# adapter_board_max86916.net
KiCad netlist of a schematic drawn in EAGLE
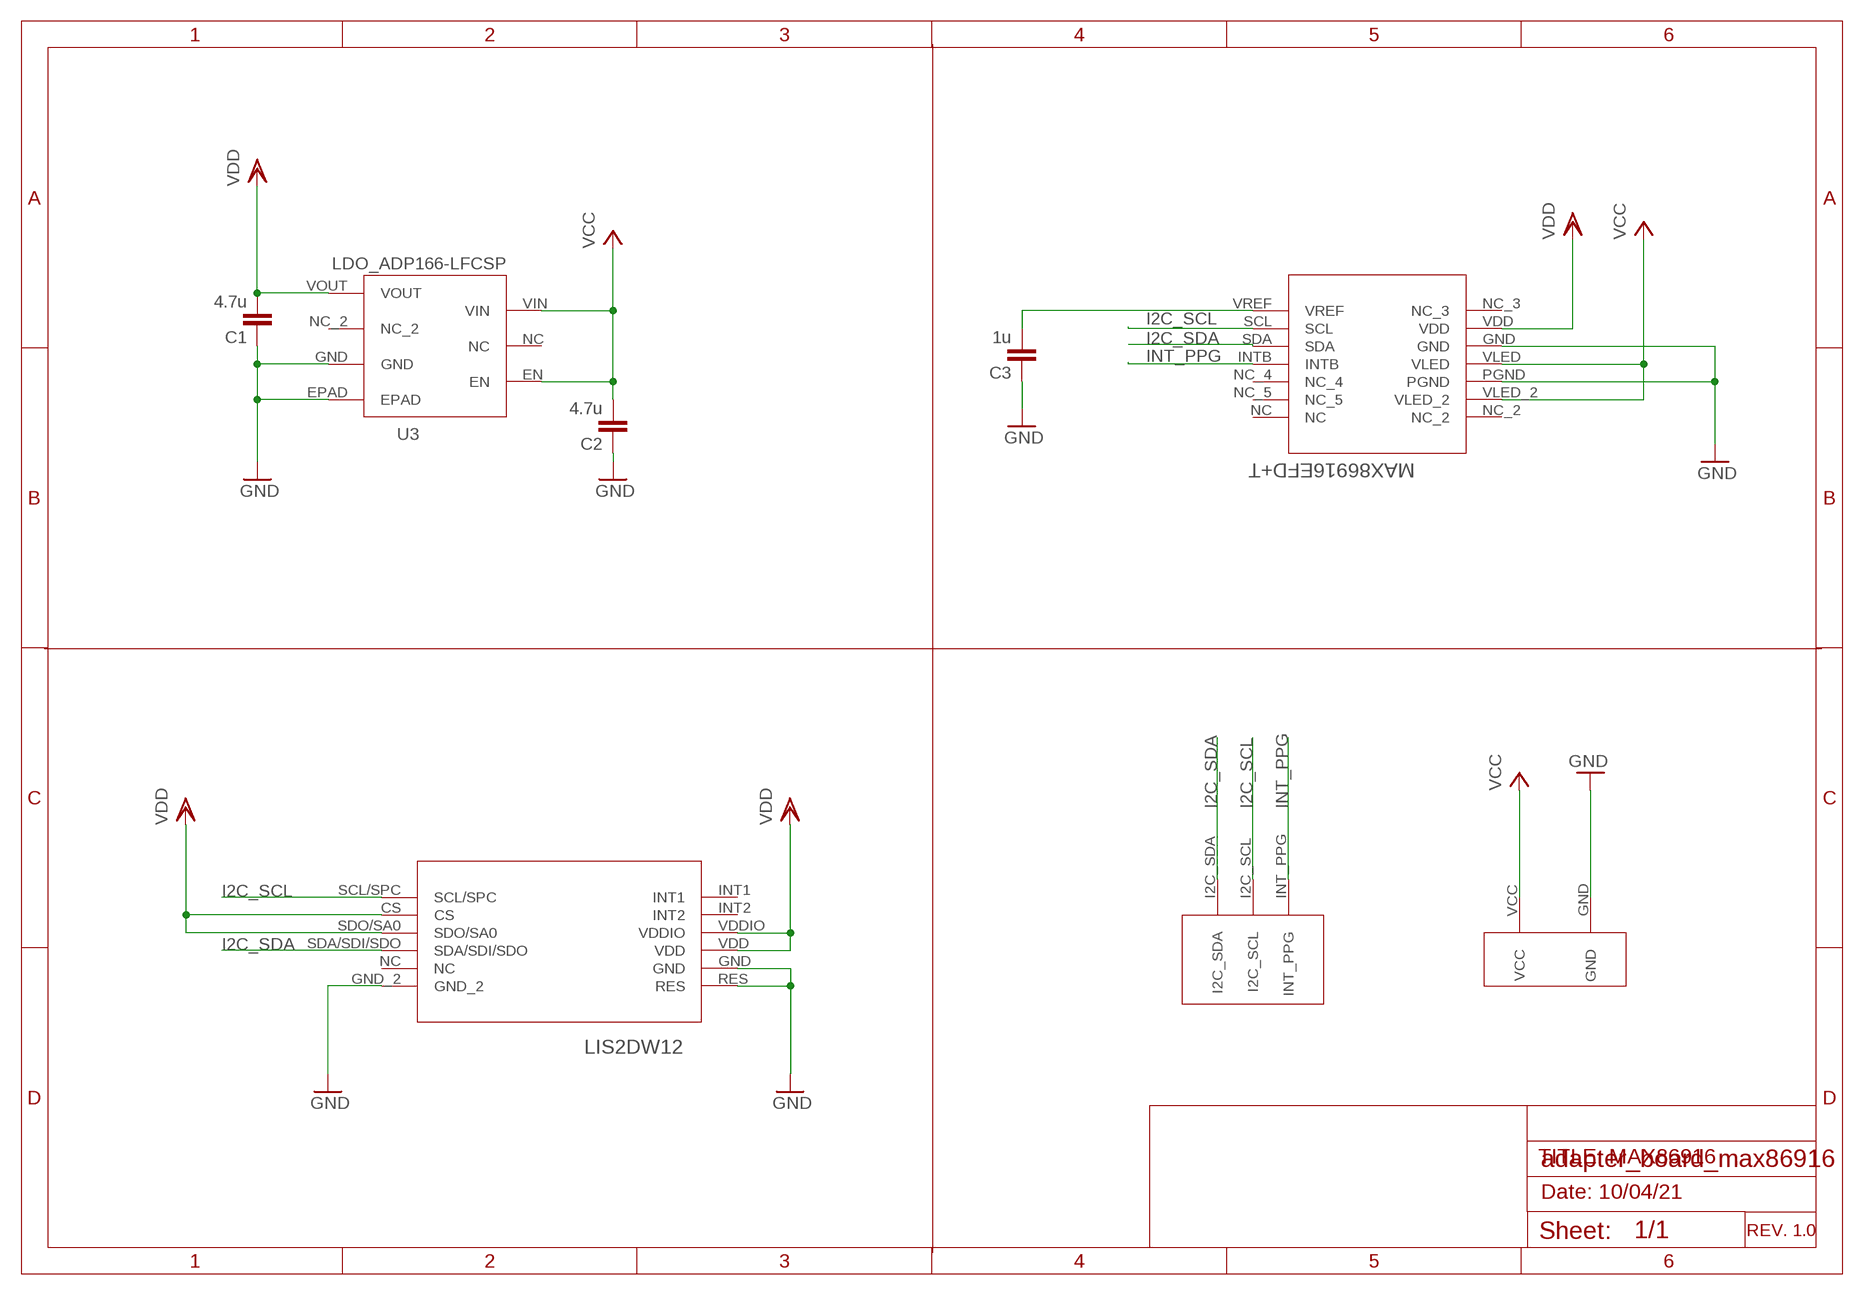
[diagram p0: schematic, sheet 1]

(export (version "E")
  (design (tool "Eeschema 10.0.6"))
  (components
    (comp (ref "C1")
      (value "4.7u")
      (footprint "eagle-import:221E_PASSIVES_C0402")
      (libsource (lib "eagle-import") (part "221E_PASSIVES_C0402"))
    )
    (comp (ref "C2")
      (value "4.7u")
      (footprint "eagle-import:221E_PASSIVES_C0402")
      (libsource (lib "eagle-import") (part "221E_PASSIVES_C0402"))
    )
    (comp (ref "C3")
      (value "1u")
      (footprint "eagle-import:221E_PASSIVES_C0402")
      (libsource (lib "eagle-import") (part "221E_PASSIVES_C0402"))
    )
    (comp (ref "U$1")
      (value "PAD_2")
      (footprint "eagle-import:PAD_2")
      (libsource (lib "eagle-import") (part "PAD_2"))
    )
    (comp (ref "U$2")
      (value "PAD_3")
      (footprint "eagle-import:PAD_3")
      (libsource (lib "eagle-import") (part "PAD_3"))
    )
    (comp (ref "U1")
      (value "MAX86916EFD+T")
      (footprint "eagle-import:21-100325_90-100122")
      (fields (field (name "COPYRIGHT") "Copyright (C) 2018 Accelerated Designs. All rights reserved"))
      (libsource (lib "eagle-import") (part "MAX86916EFD+T"))
    )
    (comp (ref "U2")
      (value "LIS2DW12")
      (footprint "eagle-import:LIS2DW12_LGA-12_2X2X0P7_STM")
      (libsource (lib "eagle-import") (part "LIS2DW12"))
    )
    (comp (ref "U3")
      (value "LDO_ADP166-LFCSP")
      (footprint "eagle-import:ADP166-LFCSP")
      (fields (field (name "SPICEPREFIX") "X"))
      (libsource (lib "eagle-import") (part "LDO_ADP166-LFCSP"))
    )
  )
  (nets
    (net (code "1") (name "/I2C_SCL") (class "Default")
      (node (ref "U$2") (pin "I2C_SCL") (pinfunction "I2C_SCL_I2C_SCL") (pintype "bidirectional"))
      (node (ref "U1") (pin "SCL") (pinfunction "SCL_SCL") (pintype "input"))
      (node (ref "U2") (pin "SCL/SPC") (pinfunction "SCL/SPC_SCL/SPC") (pintype "bidirectional"))
    )
    (net (code "2") (name "/I2C_SDA") (class "Default")
      (node (ref "U$2") (pin "I2C_SDA") (pinfunction "I2C_SDA_I2C_SDA") (pintype "bidirectional"))
      (node (ref "U1") (pin "SDA") (pinfunction "SDA_SDA") (pintype "bidirectional"))
      (node (ref "U2") (pin "SDA/SDI/SDO") (pinfunction "SDA/SDI/SDO_SDA/SDI/SDO") (pintype "bidirectional"))
    )
    (net (code "3") (name "/INT_PPG") (class "Default")
      (node (ref "U$2") (pin "INT_PPG") (pinfunction "INT_PPG_INT_PPG") (pintype "bidirectional"))
      (node (ref "U1") (pin "INTB") (pinfunction "INTB_INTB") (pintype "output"))
    )
    (net (code "4") (name "GND") (class "Default")
      (node (ref "C1") (pin "P$1") (pinfunction "1_P$1") (pintype "passive"))
      (node (ref "C2") (pin "P$1") (pinfunction "1_P$1") (pintype "passive"))
      (node (ref "C3") (pin "P$1") (pinfunction "1_P$1") (pintype "passive"))
      (node (ref "U$1") (pin "GND") (pinfunction "GND_GND") (pintype "bidirectional"))
      (node (ref "U1") (pin "GND") (pinfunction "GND_GND") (pintype "power_in"))
      (node (ref "U1") (pin "PGND") (pinfunction "PGND_PGND") (pintype "power_in"))
      (node (ref "U2") (pin "GND") (pinfunction "GND_GND") (pintype "passive"))
      (node (ref "U2") (pin "GND_2") (pinfunction "GND_2_GND_2") (pintype "passive"))
      (node (ref "U2") (pin "RES") (pinfunction "RES_RES") (pintype "passive"))
      (node (ref "U3") (pin "EPAD") (pinfunction "EPAD_EPAD") (pintype "bidirectional"))
      (node (ref "U3") (pin "GND") (pinfunction "GND_GND") (pintype "power_in"))
    )
    (net (code "5") (name "Net-(C3-2)") (class "Default")
      (node (ref "C3") (pin "P$2") (pinfunction "2_P$2") (pintype "passive"))
      (node (ref "U1") (pin "VREF") (pinfunction "VREF_VREF") (pintype "passive"))
    )
    (net (code "6") (name "VCC") (class "Default")
      (node (ref "C2") (pin "P$2") (pinfunction "2_P$2") (pintype "passive"))
      (node (ref "U$1") (pin "VCC") (pinfunction "VCC_VCC") (pintype "bidirectional"))
      (node (ref "U1") (pin "VLED") (pinfunction "VLED_VLED") (pintype "input"))
      (node (ref "U1") (pin "VLED_2") (pinfunction "VLED_2_VLED_2") (pintype "input"))
      (node (ref "U3") (pin "EN") (pinfunction "EN_EN") (pintype "input"))
      (node (ref "U3") (pin "VIN") (pinfunction "VIN_VIN") (pintype "bidirectional"))
    )
    (net (code "7") (name "VDD") (class "Default")
      (node (ref "C1") (pin "P$2") (pinfunction "2_P$2") (pintype "passive"))
      (node (ref "U1") (pin "VDD") (pinfunction "VDD_VDD") (pintype "power_in"))
      (node (ref "U2") (pin "CS") (pinfunction "CS_CS") (pintype "input"))
      (node (ref "U2") (pin "SDO/SA0") (pinfunction "SDO/SA0_SDO/SA0") (pintype "bidirectional"))
      (node (ref "U2") (pin "VDD") (pinfunction "VDD_VDD") (pintype "power_in"))
      (node (ref "U2") (pin "VDDIO") (pinfunction "VDDIO_VDDIO") (pintype "power_in"))
      (node (ref "U3") (pin "VOUT") (pinfunction "VOUT_VOUT") (pintype "bidirectional"))
    )
    (net (code "8") (name "unconnected-(U1-PadNC)") (class "Default")
      (node (ref "U1") (pin "NC") (pinfunction "NC_NC") (pintype "no_connect"))
    )
    (net (code "9") (name "unconnected-(U1-PadNC_2)") (class "Default")
      (node (ref "U1") (pin "NC_2") (pinfunction "NC_2_NC_2") (pintype "no_connect"))
    )
    (net (code "10") (name "unconnected-(U1-PadNC_3)") (class "Default")
      (node (ref "U1") (pin "NC_3") (pinfunction "NC_3_NC_3") (pintype "no_connect"))
    )
    (net (code "11") (name "unconnected-(U1-PadNC_4)") (class "Default")
      (node (ref "U1") (pin "NC_4") (pinfunction "NC_4_NC_4") (pintype "no_connect"))
    )
    (net (code "12") (name "unconnected-(U1-PadNC_5)") (class "Default")
      (node (ref "U1") (pin "NC_5") (pinfunction "NC_5_NC_5") (pintype "no_connect"))
    )
    (net (code "13") (name "unconnected-(U2-PadINT1)") (class "Default")
      (node (ref "U2") (pin "INT1") (pinfunction "INT1_INT1") (pintype "output"))
    )
    (net (code "14") (name "unconnected-(U2-PadINT2)") (class "Default")
      (node (ref "U2") (pin "INT2") (pinfunction "INT2_INT2") (pintype "output"))
    )
    (net (code "15") (name "unconnected-(U2-PadNC)") (class "Default")
      (node (ref "U2") (pin "NC") (pinfunction "NC_NC") (pintype "no_connect"))
    )
    (net (code "16") (name "unconnected-(U3-PadNC)") (class "Default")
      (node (ref "U3") (pin "NC") (pinfunction "NC_NC") (pintype "no_connect"))
    )
    (net (code "17") (name "unconnected-(U3-PadNC_2)") (class "Default")
      (node (ref "U3") (pin "NC_2") (pinfunction "NC_2_NC_2") (pintype "no_connect"))
    )
  )
)
